# PCB_Schematic.net
KiCad netlist of a schematic drawn in Altium Designer
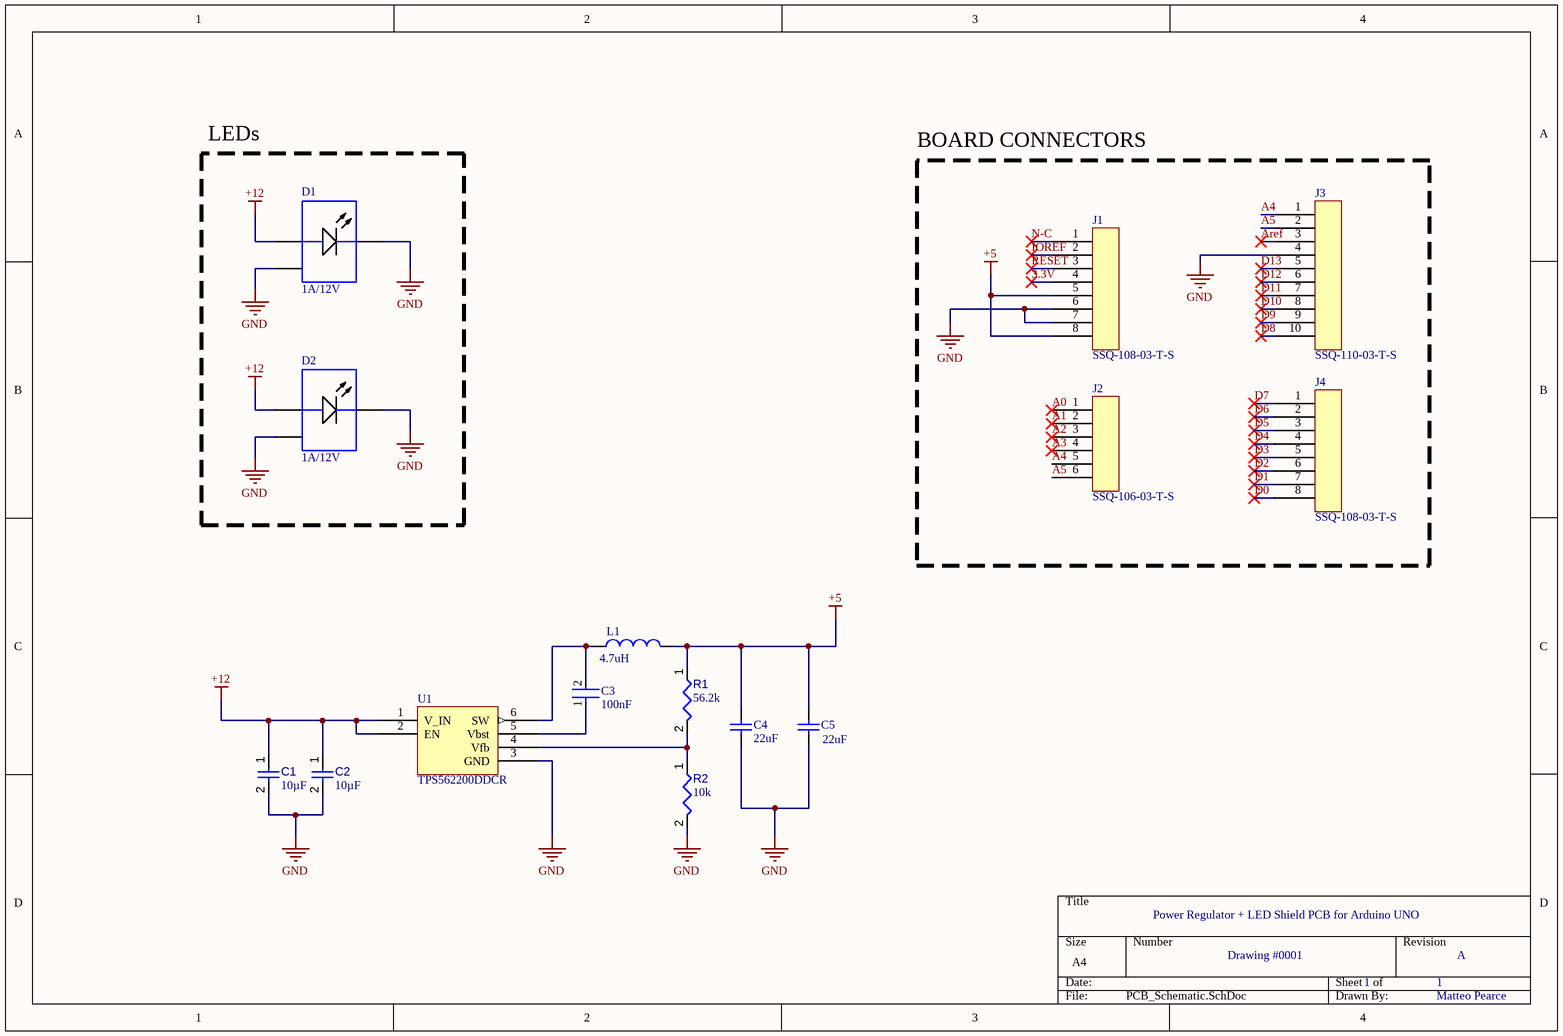
[diagram p0: PCB_Schematic.SchDoc]

(export (version "E")
  (design (tool "Eeschema 10.0.6"))
  (components
    (comp (ref "C1")
      (value "10µF")
      (footprint "CAPC2012X10N")
      (fields (field (name "Comment") "C2012X5R1V106K085AC"))
      (libsource (lib "Matteo Pearce") (part "CAP-NP-2"))
    )
    (comp (ref "C2")
      (value "10µF")
      (footprint "CAPC2012X10N")
      (fields (field (name "Comment") "C2012X5R1V106K085AC"))
      (libsource (lib "Matteo Pearce") (part "CAP-NP-2"))
    )
    (comp (ref "C3")
      (value "100nF")
      (footprint "FP-CC0805-0_85-MFG")
      (description "CAP CER 0.1UF 25V X7R 0805")
      (fields (field (name "MANUFACTURER PART NUMBER") "CC0805KRX7R8BB104") (field (name "TOLERANCE") "0.1"))
      (libsource (lib "Altium Content Vault") (part "11868f565c42a9108669ba33697ecf6"))
    )
    (comp (ref "C4")
      (value "22uF")
      (footprint "CAPC1608X100X20ML10")
      (description "Chip Capacitor, 22 uF, +/- 20%, 10 V, -55 to 85 degC, 0603 (1608 Metric), RoHS, Tape and Reel")
      (fields (field (name "MANUFACTURER") "TDK") (field (name "TOLERANCE") "±20%"))
      (libsource (lib "Altium Content Vault") (part "CAP-NP-2"))
    )
    (comp (ref "C5")
      (value "22uF")
      (footprint "CAPC1608X100X20ML10")
      (description "Chip Capacitor, 22 uF, +/- 20%, 10 V, -55 to 85 degC, 0603 (1608 Metric), RoHS, Tape and Reel")
      (fields (field (name "MANUFACTURER") "TDK") (field (name "TOLERANCE") "±20%"))
      (libsource (lib "Altium Content Vault") (part "CAP-NP-2"))
    )
    (comp (ref "D1")
      (value "1A/12V")
      (footprint "CREE-MK-R-2_V")
      (description "LED, White, 12 V, 2-Pin SMD, RoHS, Tape and Reel")
      (libsource (lib "Altium Content Vault") (part "LED_WHITE-3"))
    )
    (comp (ref "D2")
      (value "1A/12V")
      (footprint "CREE-MK-R-2_V")
      (description "LED, White, 12 V, 2-Pin SMD, RoHS, Tape and Reel")
      (libsource (lib "Altium Content Vault") (part "LED_WHITE-3"))
    )
    (comp (ref "J1")
      (value "SSQ-108-03-T-S")
      (footprint "SSQ-106-03-T-S-Footprint-2")
      (libsource (lib "Matteo Pearce") (part "SSQ-108-03-T-S-Symbol-1"))
    )
    (comp (ref "J2")
      (value "SSQ-106-03-T-S")
      (footprint "SSQ-106-03-T-S-Footprint-2")
      (libsource (lib "Matteo Pearce") (part "SSQ-106-03-T-S-Symbol-1"))
    )
    (comp (ref "J3")
      (value "SSQ-110-03-T-S")
      (footprint "SSQ-110-03-T-S-Footprint-2")
      (libsource (lib "Matteo Pearce") (part "SSQ-110-03-T-S-Symbol-1"))
    )
    (comp (ref "J4")
      (value "SSQ-108-03-T-S")
      (footprint "SSQ-106-03-T-S-Footprint-2")
      (libsource (lib "Matteo Pearce") (part "SSQ-108-03-T-S-Symbol-1"))
    )
    (comp (ref "L1")
      (value "4.7uH")
      (footprint "INDP6060X45N")
      (description "General Purpose Inductor, 4.7uH, 30%, 1 Element, Ferrite-Core, SMD, 2424")
      (fields (field (name "TOLERANCE") "30%"))
      (libsource (lib "Matteo Pearce") (part "IND-2"))
    )
    (comp (ref "R1")
      (value "56.2k")
      (footprint "RESC0603X03N")
      (fields
        (field (name "TOLERANCE") "1%")
        (field (name "POWER") "50mW")
        (field (name "Comment") "RC0201FR-0756K2L")
      )
      (libsource (lib "Matteo Pearce") (part "RES-2"))
    )
    (comp (ref "R2")
      (value "10k")
      (footprint "CAPC0603X03N")
      (fields
        (field (name "POWER") "50mW")
        (field (name "TOLERANCE") "1%")
        (field (name "Comment") "RC0201FR-0710KL")
      )
      (libsource (lib "Matteo Pearce") (part "RES-2"))
    )
    (comp (ref "U1")
      (value "TPS562200DDCR")
      (footprint "SOT95P280X110-6N")
      (description "Switching Regulator, 2A, 650kHz Switching Freq-Max, PDSO6")
      (libsource (lib "Matteo Pearce") (part "TPS562200DDCR-Symbol-1"))
    )
  )
  (nets
    (net (code "1") (name "+5") (class "Default")
      (node (ref "C4") (pin "1") (pinfunction "1_1") (pintype "passive"))
      (node (ref "C5") (pin "1") (pinfunction "1_1") (pintype "passive"))
      (node (ref "J1") (pin "5") (pintype "passive"))
      (node (ref "J1") (pin "8") (pintype "passive"))
      (node (ref "L1") (pin "2") (pinfunction "2_2") (pintype "passive"))
      (node (ref "R1") (pin "1") (pinfunction "1_1") (pintype "passive"))
    )
    (net (code "2") (name "+12") (class "Default")
      (node (ref "C1") (pin "1") (pinfunction "1_1") (pintype "passive"))
      (node (ref "C2") (pin "1") (pinfunction "1_1") (pintype "passive"))
      (node (ref "D1") (pin "1") (pinfunction "A_1") (pintype "passive"))
      (node (ref "D2") (pin "1") (pinfunction "A_1") (pintype "passive"))
      (node (ref "U1") (pin "1") (pinfunction "V_IN_1") (pintype "power_in"))
      (node (ref "U1") (pin "2") (pinfunction "EN_2") (pintype "power_in"))
    )
    (net (code "3") (name "/3.3V") (class "Default")
      (node (ref "J1") (pin "4") (pintype "passive+no_connect"))
    )
    (net (code "4") (name "/A0") (class "Default") (node (ref "J2") (pin "1") (pintype "passive+no_connect")))
    (net (code "5") (name "/A1") (class "Default") (node (ref "J2") (pin "2") (pintype "passive+no_connect")))
    (net (code "6") (name "/A2") (class "Default") (node (ref "J2") (pin "3") (pintype "passive+no_connect")))
    (net (code "7") (name "/A3") (class "Default") (node (ref "J2") (pin "4") (pintype "passive+no_connect")))
    (net (code "8") (name "/A4") (class "Default")
      (node (ref "J2") (pin "5") (pintype "passive"))
      (node (ref "J3") (pin "1") (pintype "passive"))
    )
    (net (code "9") (name "/A5") (class "Default")
      (node (ref "J2") (pin "6") (pintype "passive"))
      (node (ref "J3") (pin "2") (pintype "passive"))
    )
    (net (code "10") (name "/Aref") (class "Default")
      (node (ref "J3") (pin "3") (pintype "passive+no_connect"))
    )
    (net (code "11") (name "/D0") (class "Default")
      (node (ref "J4") (pin "8") (pintype "passive+no_connect"))
    )
    (net (code "12") (name "/D1") (class "Default")
      (node (ref "J4") (pin "7") (pintype "passive+no_connect"))
    )
    (net (code "13") (name "/D2") (class "Default")
      (node (ref "J4") (pin "6") (pintype "passive+no_connect"))
    )
    (net (code "14") (name "/D3") (class "Default")
      (node (ref "J4") (pin "5") (pintype "passive+no_connect"))
    )
    (net (code "15") (name "/D4") (class "Default")
      (node (ref "J4") (pin "4") (pintype "passive+no_connect"))
    )
    (net (code "16") (name "/D5") (class "Default")
      (node (ref "J4") (pin "3") (pintype "passive+no_connect"))
    )
    (net (code "17") (name "/D6") (class "Default")
      (node (ref "J4") (pin "2") (pintype "passive+no_connect"))
    )
    (net (code "18") (name "/D7") (class "Default")
      (node (ref "J4") (pin "1") (pintype "passive+no_connect"))
    )
    (net (code "19") (name "/D8") (class "Default")
      (node (ref "J3") (pin "10") (pintype "passive+no_connect"))
    )
    (net (code "20") (name "/D9") (class "Default")
      (node (ref "J3") (pin "9") (pintype "passive+no_connect"))
    )
    (net (code "21") (name "/D10") (class "Default")
      (node (ref "J3") (pin "8") (pintype "passive+no_connect"))
    )
    (net (code "22") (name "/D11") (class "Default")
      (node (ref "J3") (pin "7") (pintype "passive+no_connect"))
    )
    (net (code "23") (name "/D12") (class "Default")
      (node (ref "J3") (pin "6") (pintype "passive+no_connect"))
    )
    (net (code "24") (name "/D13") (class "Default")
      (node (ref "J3") (pin "5") (pintype "passive+no_connect"))
    )
    (net (code "25") (name "/IOREF") (class "Default")
      (node (ref "J1") (pin "2") (pintype "passive+no_connect"))
    )
    (net (code "26") (name "/N-C") (class "Default")
      (node (ref "J1") (pin "1") (pintype "passive+no_connect"))
    )
    (net (code "27") (name "/RESET") (class "Default")
      (node (ref "J1") (pin "3") (pintype "passive+no_connect"))
    )
    (net (code "28") (name "GND") (class "Default")
      (node (ref "C1") (pin "2") (pinfunction "2_2") (pintype "passive"))
      (node (ref "C2") (pin "2") (pinfunction "2_2") (pintype "passive"))
      (node (ref "C4") (pin "2") (pinfunction "2_2") (pintype "passive"))
      (node (ref "C5") (pin "2") (pinfunction "2_2") (pintype "passive"))
      (node (ref "D1") (pin "2") (pinfunction "K_2") (pintype "passive"))
      (node (ref "D1") (pin "3") (pinfunction "EP_3") (pintype "passive"))
      (node (ref "D2") (pin "2") (pinfunction "K_2") (pintype "passive"))
      (node (ref "D2") (pin "3") (pinfunction "EP_3") (pintype "passive"))
      (node (ref "J1") (pin "6") (pintype "passive"))
      (node (ref "J1") (pin "7") (pintype "passive"))
      (node (ref "J3") (pin "4") (pintype "passive"))
      (node (ref "R2") (pin "2") (pinfunction "2_2") (pintype "passive"))
      (node (ref "U1") (pin "3") (pinfunction "GND_3") (pintype "power_in"))
    )
    (net (code "29") (name "Net-(U1-SW)") (class "Default")
      (node (ref "C3") (pin "2") (pinfunction "2_2") (pintype "passive"))
      (node (ref "L1") (pin "1") (pinfunction "1_1") (pintype "passive"))
      (node (ref "U1") (pin "6") (pinfunction "SW_6") (pintype "output"))
    )
    (net (code "30") (name "Net-(U1-Vbst)") (class "Default")
      (node (ref "C3") (pin "1") (pinfunction "1_1") (pintype "passive"))
      (node (ref "U1") (pin "5") (pinfunction "Vbst_5") (pintype "passive"))
    )
    (net (code "31") (name "Net-(U1-Vfb)") (class "Default")
      (node (ref "R1") (pin "2") (pinfunction "2_2") (pintype "passive"))
      (node (ref "R2") (pin "1") (pinfunction "1_1") (pintype "passive"))
      (node (ref "U1") (pin "4") (pinfunction "Vfb_4") (pintype "passive"))
    )
  )
)
